# 3s_BMS.net
KiCad netlist of a schematic drawn in Altium Designer
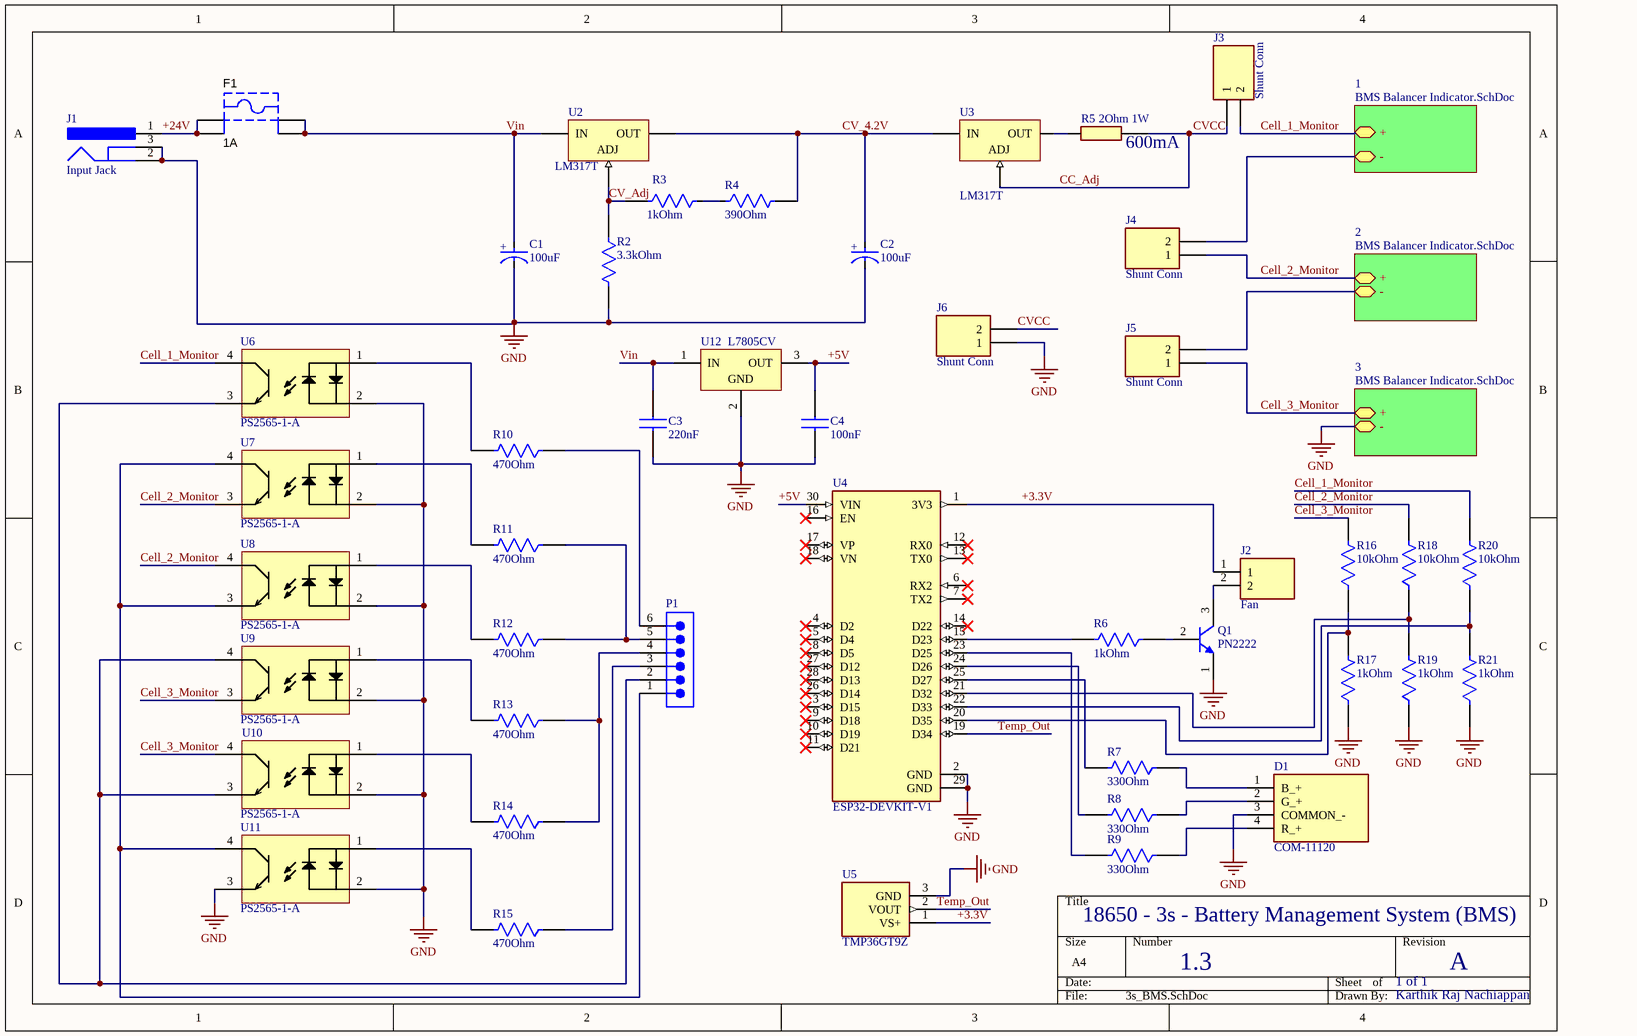
[diagram p0: 3s_BMS.SchDoc]

(export (version "E")
  (design (tool "Eeschema 10.0.6"))
  (components
    (comp (ref "C1")
      (value "100uF")
      (footprint "FP-RAD-TH-D_8_0_5-L_11_5-MFG")
      (description "Aluminum Electrolytic Capacitors (Radial Lead Type) 100uF ±20% 50V")
      (libsource (lib "Altium Content Vault") (part "a00bbbee19879c290e62620ae7e47b1"))
    )
    (comp (ref "C2")
      (value "100uF")
      (footprint "FP-RAD-TH-D_8_0_5-L_11_5-MFG")
      (description "Aluminum Electrolytic Capacitors (Radial Lead Type) 100uF ±20% 50V")
      (libsource (lib "Altium Content Vault") (part "a00bbbee19879c290e62620ae7e47b1"))
    )
    (comp (ref "C3")
      (value "220nF")
      (footprint "SamacSys:K224K20X7RF5TH5")
      (description "Capacitor")
      (fields
        (field (name "MANUFACTURER_PART_NUMBER") "K224K20X7RF5TH5")
        (field (name "MOUSER PART NUMBER") "594-K224K20X7RF5TH5")
      )
      (libsource (lib "*") (part "K224K20X7RF5TH5"))
    )
    (comp (ref "C4")
      (value "100nF")
      (footprint "SamacSys:C322C104K1R5TA")
      (description "Capacitor")
      (fields
        (field (name "MANUFACTURER_PART_NUMBER") "C322C104M5U5TA")
        (field (name "MOUSER PART NUMBER") "80-C322C104M5U")
      )
      (libsource (lib "*") (part "C322C104M5U5TA"))
    )
    (comp (ref "D1")
      (value "COM-11120")
      (footprint "SamacSys:COM11120")
      (description "LED")
      (fields (field (name "MOUSER PART NUMBER") "474-COM-11120"))
      (libsource (lib "*") (part "COM-11120"))
    )
    (comp (ref "F1")
      (value "1A")
      (footprint "KSTN-3557-2")
      (description "FUSE HOLDER, PCB MOUNT, 500VAC, 20A, ROHS")
      (fields (field (name "VOLTAGE") "500V") (field (name "MANUFACTURER") "Keystone-Electronics"))
      (libsource (lib "Altium Content Vault") (part "FUSE_HOLDER-4"))
    )
    (comp (ref "J1")
      (value "Input Jack")
      (footprint "CUI-PJ-002A_V")
      (fields (field (name "MANUFACTURER") "CUIInc."))
      (libsource (lib "Altium Content Vault") (part "JACK-2CD3-RN_B"))
    )
    (comp (ref "J2")
      (value "Fan")
      (footprint "SamacSys:HDRV2W67P0X254_1X2_467X234X823P")
      (description "Connector")
      (fields
        (field (name "MANUFACTURER_PART_NUMBER") "5-146277-2")
        (field (name "MOUSER PART NUMBER") "571-5-146277-2")
      )
      (libsource (lib "") (part "5-146277-2_2"))
    )
    (comp (ref "J3")
      (value "Shunt Conn")
      (footprint "SamacSys:HDRV2W67P0X254_1X2_467X234X823P")
      (description "Connector")
      (fields
        (field (name "MANUFACTURER_PART_NUMBER") "5-146277-2")
        (field (name "MOUSER PART NUMBER") "571-5-146277-2")
      )
      (libsource (lib "*") (part "5-146277-2"))
    )
    (comp (ref "J4")
      (value "Shunt Conn")
      (footprint "SamacSys:HDRV2W67P0X254_1X2_467X234X823P")
      (description "Connector")
      (fields
        (field (name "MANUFACTURER_PART_NUMBER") "5-146277-2")
        (field (name "MOUSER PART NUMBER") "571-5-146277-2")
      )
      (libsource (lib "") (part "5-146277-2_1"))
    )
    (comp (ref "J5")
      (value "Shunt Conn")
      (footprint "SamacSys:HDRV2W67P0X254_1X2_467X234X823P")
      (description "Connector")
      (fields
        (field (name "MANUFACTURER_PART_NUMBER") "5-146277-2")
        (field (name "MOUSER PART NUMBER") "571-5-146277-2")
      )
      (libsource (lib "") (part "5-146277-2_1"))
    )
    (comp (ref "J6")
      (value "Shunt Conn")
      (footprint "SamacSys:HDRV2W67P0X254_1X2_467X234X823P")
      (description "Connector")
      (fields
        (field (name "MANUFACTURER_PART_NUMBER") "5-146277-2")
        (field (name "MOUSER PART NUMBER") "571-5-146277-2")
      )
      (libsource (lib "") (part "5-146277-2_1"))
    )
    (comp (ref "P1")
      (value "~")
      (footprint "SMTC-TSW-106-07-X-S")
      (description "0.025\" SQ Post Header, Through-hole, Vertical, -55 to 125 degC, 2.54 mm Pitch, 6-Pin, Male, RoHS")
      (fields (field (name "MANUFACTURER") "Samtec") (field (name "PARTNUMBER") "TSW-106-07-G-S"))
      (libsource (lib "Altium Content Vault") (part "SMTC-TSW-106-X-X-S-X"))
    )
    (comp (ref "Q1")
      (value "PN2222")
      (footprint "FAIR-TO-92-3")
      (description "NPN General-Purpose Amplifier, 40 V, -55 to 150 degC, 3-Pin TO-92, RoHS, Tape and Reel")
      (fields (field (name "MANUFACTURER") "FairchildSemiconductor"))
      (libsource (lib "Altium Content Vault") (part "BJT-NPN-EBC-3"))
    )
    (comp (ref "R2")
      (value "3.3kOhm")
      (footprint "FP-MRS25-MFG")
      (description "RES 1K OHM 0.6W 1% AXIAL")
      (fields (field (name "TOLERANCE") "1%"))
      (libsource (lib "Altium Content Vault") (part "1029c3af85768c4190bb7ad29bc67b5"))
    )
    (comp (ref "R3")
      (value "1kOhm")
      (footprint "FP-MRS25-MFG")
      (description "RES 1K OHM 0.6W 1% AXIAL")
      (fields (field (name "TOLERANCE") "1%"))
      (libsource (lib "Altium Content Vault") (part "1029c3af85768c4190bb7ad29bc67b5"))
    )
    (comp (ref "R4")
      (value "390Ohm")
      (footprint "FP-MRS25-MFG")
      (description "RES 1K OHM 0.6W 1% AXIAL")
      (fields (field (name "TOLERANCE") "1%"))
      (libsource (lib "Altium Content Vault") (part "1029c3af85768c4190bb7ad29bc67b5"))
    )
    (comp (ref "R5")
      (value "2Ohm 1W")
      (footprint "SamacSys:RESAD1650W63L650D250")
      (description "Resistor")
      (fields
        (field (name "MANUFACTURER_PART_NUMBER") "PR01000102008JR500")
        (field (name "MOUSER PART NUMBER") "594-5073NW2R000J")
      )
      (libsource (lib "*") (part "PR01000102008JR500"))
    )
    (comp (ref "R6")
      (value "1kOhm")
      (footprint "FP-MRS25-MFG")
      (description "RES 1K OHM 0.6W 1% AXIAL")
      (fields (field (name "TOLERANCE") "1%"))
      (libsource (lib "Altium Content Vault") (part "1029c3af85768c4190bb7ad29bc67b5"))
    )
    (comp (ref "R7")
      (value "330Ohm")
      (footprint "FP-MRS25-MFG")
      (description "RES 1K OHM 0.6W 1% AXIAL")
      (fields (field (name "TOLERANCE") "1%"))
      (libsource (lib "Altium Content Vault") (part "1029c3af85768c4190bb7ad29bc67b5"))
    )
    (comp (ref "R8")
      (value "330Ohm")
      (footprint "FP-MRS25-MFG")
      (description "RES 1K OHM 0.6W 1% AXIAL")
      (fields (field (name "TOLERANCE") "1%"))
      (libsource (lib "Altium Content Vault") (part "1029c3af85768c4190bb7ad29bc67b5"))
    )
    (comp (ref "R9")
      (value "330Ohm")
      (footprint "FP-MRS25-MFG")
      (description "RES 1K OHM 0.6W 1% AXIAL")
      (fields (field (name "TOLERANCE") "1%"))
      (libsource (lib "Altium Content Vault") (part "1029c3af85768c4190bb7ad29bc67b5"))
    )
    (comp (ref "R10")
      (value "470Ohm")
      (footprint "FP-MRS25-MFG")
      (description "RES 1K OHM 0.6W 1% AXIAL")
      (fields (field (name "TOLERANCE") "1%"))
      (libsource (lib "Altium Content Vault") (part "1029c3af85768c4190bb7ad29bc67b5"))
    )
    (comp (ref "R11")
      (value "470Ohm")
      (footprint "FP-MRS25-MFG")
      (description "RES 1K OHM 0.6W 1% AXIAL")
      (fields (field (name "TOLERANCE") "1%"))
      (libsource (lib "Altium Content Vault") (part "1029c3af85768c4190bb7ad29bc67b5"))
    )
    (comp (ref "R12")
      (value "470Ohm")
      (footprint "FP-MRS25-MFG")
      (description "RES 1K OHM 0.6W 1% AXIAL")
      (fields (field (name "TOLERANCE") "1%"))
      (libsource (lib "Altium Content Vault") (part "1029c3af85768c4190bb7ad29bc67b5"))
    )
    (comp (ref "R13")
      (value "470Ohm")
      (footprint "FP-MRS25-MFG")
      (description "RES 1K OHM 0.6W 1% AXIAL")
      (fields (field (name "TOLERANCE") "1%"))
      (libsource (lib "Altium Content Vault") (part "1029c3af85768c4190bb7ad29bc67b5"))
    )
    (comp (ref "R14")
      (value "470Ohm")
      (footprint "FP-MRS25-MFG")
      (description "RES 1K OHM 0.6W 1% AXIAL")
      (fields (field (name "TOLERANCE") "1%"))
      (libsource (lib "Altium Content Vault") (part "1029c3af85768c4190bb7ad29bc67b5"))
    )
    (comp (ref "R15")
      (value "470Ohm")
      (footprint "FP-MRS25-MFG")
      (description "RES 1K OHM 0.6W 1% AXIAL")
      (fields (field (name "TOLERANCE") "1%"))
      (libsource (lib "Altium Content Vault") (part "1029c3af85768c4190bb7ad29bc67b5"))
    )
    (comp (ref "R16")
      (value "10kOhm")
      (footprint "FP-MRS25-MFG")
      (description "RES 1K OHM 0.6W 1% AXIAL")
      (fields (field (name "TOLERANCE") "1%"))
      (libsource (lib "Altium Content Vault") (part "1029c3af85768c4190bb7ad29bc67b5"))
    )
    (comp (ref "R17")
      (value "1kOhm")
      (footprint "FP-MRS25-MFG")
      (description "RES 1K OHM 0.6W 1% AXIAL")
      (fields (field (name "TOLERANCE") "1%"))
      (libsource (lib "Altium Content Vault") (part "1029c3af85768c4190bb7ad29bc67b5"))
    )
    (comp (ref "R18")
      (value "10kOhm")
      (footprint "FP-MRS25-MFG")
      (description "RES 1K OHM 0.6W 1% AXIAL")
      (fields (field (name "TOLERANCE") "1%"))
      (libsource (lib "Altium Content Vault") (part "1029c3af85768c4190bb7ad29bc67b5"))
    )
    (comp (ref "R19")
      (value "1kOhm")
      (footprint "FP-MRS25-MFG")
      (description "RES 1K OHM 0.6W 1% AXIAL")
      (fields (field (name "TOLERANCE") "1%"))
      (libsource (lib "Altium Content Vault") (part "1029c3af85768c4190bb7ad29bc67b5"))
    )
    (comp (ref "R20")
      (value "10kOhm")
      (footprint "FP-MRS25-MFG")
      (description "RES 1K OHM 0.6W 1% AXIAL")
      (fields (field (name "TOLERANCE") "1%"))
      (libsource (lib "Altium Content Vault") (part "1029c3af85768c4190bb7ad29bc67b5"))
    )
    (comp (ref "R21")
      (value "1kOhm")
      (footprint "FP-MRS25-MFG")
      (description "RES 1K OHM 0.6W 1% AXIAL")
      (fields (field (name "TOLERANCE") "1%"))
      (libsource (lib "Altium Content Vault") (part "1029c3af85768c4190bb7ad29bc67b5"))
    )
    (comp (ref "U2")
      (value "LM317T")
      (footprint "TO-220")
      (description "1.5A, 1.2V to 37V Adjustable Voltage Regulator, 3-Pin TO-220")
      (libsource (lib "Altium Content Vault") (part "PM-REG-117-SIL3"))
    )
    (comp (ref "U3")
      (value "LM317T")
      (footprint "TO-220")
      (description "1.5A, 1.2V to 37V Adjustable Voltage Regulator, 3-Pin TO-220")
      (libsource (lib "Altium Content Vault") (part "PM-REG-117-SIL3"))
    )
    (comp (ref "U4")
      (value "ESP32-DEVKIT-V1")
      (footprint "MODULE_ESP32_DEVKIT_V1")
      (fields (field (name "MF") "Do it"))
      (libsource (lib "NTU") (part "ESP32-DEVKIT-V1"))
    )
    (comp (ref "U5")
      (value "TMP36GT9Z")
      (footprint "SamacSys:TO-92")
      (description "Thermistor")
      (fields (field (name "MOUSER PART NUMBER") "584-TMP36GT9Z"))
      (libsource (lib "*") (part "TMP36GT9Z"))
    )
    (comp (ref "U6")
      (value "PS2565-1-A")
      (footprint "DIP762W50P254L460H455Q4B")
      (description "PS2565-1-A Optocoupler AC-IN 1-CH Transistor DC-OUT 4-Pin PDIP Magazine")
      (libsource (lib "Altium Content Vault") (part "PS2565-1-A"))
    )
    (comp (ref "U7")
      (value "PS2565-1-A")
      (footprint "DIP762W50P254L460H455Q4B")
      (description "PS2565-1-A Optocoupler AC-IN 1-CH Transistor DC-OUT 4-Pin PDIP Magazine")
      (libsource (lib "Altium Content Vault") (part "PS2565-1-A"))
    )
    (comp (ref "U8")
      (value "PS2565-1-A")
      (footprint "DIP762W50P254L460H455Q4B")
      (description "PS2565-1-A Optocoupler AC-IN 1-CH Transistor DC-OUT 4-Pin PDIP Magazine")
      (libsource (lib "Altium Content Vault") (part "PS2565-1-A"))
    )
    (comp (ref "U9")
      (value "PS2565-1-A")
      (footprint "DIP762W50P254L460H455Q4B")
      (description "PS2565-1-A Optocoupler AC-IN 1-CH Transistor DC-OUT 4-Pin PDIP Magazine")
      (libsource (lib "Altium Content Vault") (part "PS2565-1-A"))
    )
    (comp (ref "U10")
      (value "PS2565-1-A")
      (footprint "DIP762W50P254L460H455Q4B")
      (description "PS2565-1-A Optocoupler AC-IN 1-CH Transistor DC-OUT 4-Pin PDIP Magazine")
      (libsource (lib "Altium Content Vault") (part "PS2565-1-A"))
    )
    (comp (ref "U11")
      (value "PS2565-1-A")
      (footprint "DIP762W50P254L460H455Q4B")
      (description "PS2565-1-A Optocoupler AC-IN 1-CH Transistor DC-OUT 4-Pin PDIP Magazine")
      (libsource (lib "Altium Content Vault") (part "PS2565-1-A"))
    )
    (comp (ref "U12")
      (value "L7805CV")
      (footprint "TO220")
      (description "Positive Voltage Regulator, 5V, 3-Pin TO-220")
      (libsource (lib "Altium Content Vault") (part "PM-REG-L4940-SIL3"))
    )
  )
  (nets
    (net (code "1") (name "/+3.3V") (class "Default")
      (node (ref "J2") (pin "1") (pinfunction "1_1") (pintype "passive"))
      (node (ref "U4") (pin "1") (pinfunction "3V3_1") (pintype "output"))
      (node (ref "U5") (pin "1") (pinfunction "VS+_1") (pintype "power_in"))
    )
    (net (code "2") (name "/+5V") (class "Default")
      (node (ref "C4") (pin "1") (pinfunction "+_1") (pintype "passive"))
      (node (ref "U12") (pin "3") (pinfunction "OUT_3") (pintype "power_in"))
      (node (ref "U4") (pin "30") (pinfunction "VIN_30") (pintype "input"))
    )
    (net (code "3") (name "/+24V") (class "Default")
      (node (ref "F1") (pin "1") (pinfunction "1_1") (pintype "passive"))
      (node (ref "F1") (pin "2") (pinfunction "2_2") (pintype "passive"))
      (node (ref "J1") (pin "1") (pinfunction "1_1") (pintype "passive"))
    )
    (net (code "4") (name "/-") (class "Default")
      (node (ref "J5") (pin "2") (pinfunction "2_2") (pintype "passive"))
    )
    (net (code "5") (name "/-_1") (class "Default")
      (node (ref "J4") (pin "2") (pinfunction "2_2") (pintype "passive"))
    )
    (net (code "6") (name "/CC_Adj") (class "Default")
      (node (ref "J3") (pin "1") (pinfunction "1_1") (pintype "passive"))
      (node (ref "J6") (pin "2") (pinfunction "2_2") (pintype "passive"))
      (node (ref "R5") (pin "2") (pinfunction "2_2") (pintype "passive"))
      (node (ref "U3") (pin "1") (pinfunction "ADJ_1") (pintype "input"))
    )
    (net (code "7") (name "/CV_4.2V") (class "Default")
      (node (ref "C2") (pin "2") (pinfunction "A_2") (pintype "passive"))
      (node (ref "R4") (pin "2") (pinfunction "2_2") (pintype "passive"))
      (node (ref "U2") (pin "2") (pinfunction "OUT_2") (pintype "power_in"))
      (node (ref "U3") (pin "3") (pinfunction "IN_3") (pintype "power_in"))
    )
    (net (code "8") (name "/CV_Adj") (class "Default")
      (node (ref "R2") (pin "1") (pinfunction "1_1") (pintype "passive"))
      (node (ref "R3") (pin "1") (pinfunction "1_1") (pintype "passive"))
      (node (ref "U2") (pin "1") (pinfunction "ADJ_1") (pintype "input"))
    )
    (net (code "9") (name "/Cell_1_Monitor") (class "Default")
      (node (ref "J3") (pin "2") (pinfunction "2_2") (pintype "passive"))
      (node (ref "R20") (pin "2") (pinfunction "2_2") (pintype "passive"))
      (node (ref "U6") (pin "4") (pinfunction "Collector_4") (pintype "power_in"))
    )
    (net (code "10") (name "/Cell_2_Monitor") (class "Default")
      (node (ref "J4") (pin "1") (pinfunction "1_1") (pintype "passive"))
      (node (ref "R18") (pin "2") (pinfunction "2_2") (pintype "passive"))
      (node (ref "U7") (pin "3") (pinfunction "Emitter_3") (pintype "power_in"))
      (node (ref "U8") (pin "4") (pinfunction "Collector_4") (pintype "power_in"))
    )
    (net (code "11") (name "/Cell_3_Monitor") (class "Default")
      (node (ref "J5") (pin "1") (pinfunction "1_1") (pintype "passive"))
      (node (ref "R16") (pin "2") (pinfunction "2_2") (pintype "passive"))
      (node (ref "U10") (pin "4") (pinfunction "Collector_4") (pintype "power_in"))
      (node (ref "U9") (pin "3") (pinfunction "Emitter_3") (pintype "power_in"))
    )
    (net (code "12") (name "/Temp_Out") (class "Default")
      (node (ref "U4") (pin "19") (pinfunction "D34_19") (pintype "bidirectional"))
      (node (ref "U5") (pin "2") (pinfunction "VOUT_2") (pintype "output"))
    )
    (net (code "13") (name "/Vin") (class "Default")
      (node (ref "C1") (pin "2") (pinfunction "A_2") (pintype "passive"))
      (node (ref "C3") (pin "1") (pinfunction "1_1") (pintype "passive"))
      (node (ref "F1") (pin "3") (pinfunction "3_3") (pintype "passive"))
      (node (ref "F1") (pin "4") (pinfunction "4_4") (pintype "passive"))
      (node (ref "U12") (pin "1") (pinfunction "IN_1") (pintype "power_in"))
      (node (ref "U2") (pin "3") (pinfunction "IN_3") (pintype "power_in"))
    )
    (net (code "14") (name "GND") (class "Default")
      (node (ref "C1") (pin "1") (pinfunction "C_1") (pintype "passive"))
      (node (ref "C2") (pin "1") (pinfunction "C_1") (pintype "passive"))
      (node (ref "C3") (pin "2") (pinfunction "2_2") (pintype "passive"))
      (node (ref "C4") (pin "2") (pinfunction "-_2") (pintype "passive"))
      (node (ref "D1") (pin "3") (pinfunction "COMMON_-_3") (pintype "passive"))
      (node (ref "J1") (pin "2") (pinfunction "2_2") (pintype "passive"))
      (node (ref "J1") (pin "3") (pinfunction "3_3") (pintype "passive"))
      (node (ref "J6") (pin "1") (pinfunction "1_1") (pintype "passive"))
      (node (ref "Q1") (pin "1") (pinfunction "E_1") (pintype "passive"))
      (node (ref "R17") (pin "1") (pinfunction "1_1") (pintype "passive"))
      (node (ref "R19") (pin "1") (pinfunction "1_1") (pintype "passive"))
      (node (ref "R2") (pin "2") (pinfunction "2_2") (pintype "passive"))
      (node (ref "R21") (pin "1") (pinfunction "1_1") (pintype "passive"))
      (node (ref "U10") (pin "2") (pinfunction "Cathode_2") (pintype "passive"))
      (node (ref "U11") (pin "2") (pinfunction "Cathode_2") (pintype "passive"))
      (node (ref "U11") (pin "3") (pinfunction "Emitter_3") (pintype "power_in"))
      (node (ref "U12") (pin "2") (pinfunction "GND_2") (pintype "power_in"))
      (node (ref "U4") (pin "2") (pinfunction "GND_2") (pintype "power_in"))
      (node (ref "U4") (pin "29") (pinfunction "GND_29") (pintype "power_in"))
      (node (ref "U5") (pin "3") (pinfunction "GND_3") (pintype "power_in"))
      (node (ref "U6") (pin "2") (pinfunction "Cathode_2") (pintype "passive"))
      (node (ref "U7") (pin "2") (pinfunction "Cathode_2") (pintype "passive"))
      (node (ref "U8") (pin "2") (pinfunction "Cathode_2") (pintype "passive"))
      (node (ref "U9") (pin "2") (pinfunction "Cathode_2") (pintype "passive"))
    )
    (net (code "15") (name "Net-(D1-B_+)") (class "Default")
      (node (ref "D1") (pin "1") (pinfunction "B_+_1") (pintype "passive"))
      (node (ref "R7") (pin "1") (pinfunction "1_1") (pintype "passive"))
    )
    (net (code "16") (name "Net-(D1-G_+)") (class "Default")
      (node (ref "D1") (pin "2") (pinfunction "G_+_2") (pintype "passive"))
      (node (ref "R8") (pin "1") (pinfunction "1_1") (pintype "passive"))
    )
    (net (code "17") (name "Net-(D1-R_+)") (class "Default")
      (node (ref "D1") (pin "4") (pinfunction "R_+_4") (pintype "passive"))
      (node (ref "R9") (pin "1") (pinfunction "1_1") (pintype "passive"))
    )
    (net (code "18") (name "Net-(P1-Pad3)") (class "Default")
      (node (ref "P1") (pin "3") (pinfunction "3_3") (pintype "passive"))
      (node (ref "R15") (pin "1") (pinfunction "1_1") (pintype "passive"))
    )
    (net (code "19") (name "Net-(P1-Pad4)") (class "Default")
      (node (ref "P1") (pin "4") (pinfunction "4_4") (pintype "passive"))
      (node (ref "R13") (pin "1") (pinfunction "1_1") (pintype "passive"))
      (node (ref "R14") (pin "1") (pinfunction "1_1") (pintype "passive"))
    )
    (net (code "20") (name "Net-(P1-Pad5)") (class "Default")
      (node (ref "P1") (pin "5") (pinfunction "5_5") (pintype "passive"))
      (node (ref "R11") (pin "1") (pinfunction "1_1") (pintype "passive"))
      (node (ref "R12") (pin "1") (pinfunction "1_1") (pintype "passive"))
    )
    (net (code "21") (name "Net-(P1-Pad6)") (class "Default")
      (node (ref "P1") (pin "6") (pinfunction "6_6") (pintype "passive"))
      (node (ref "R10") (pin "1") (pinfunction "1_1") (pintype "passive"))
    )
    (net (code "22") (name "Net-(Q1-B)") (class "Default")
      (node (ref "Q1") (pin "2") (pinfunction "B_2") (pintype "passive"))
      (node (ref "R6") (pin "1") (pinfunction "1_1") (pintype "passive"))
    )
    (net (code "23") (name "Net-(Q1-C)") (class "Default")
      (node (ref "J2") (pin "2") (pinfunction "2_2") (pintype "passive"))
      (node (ref "Q1") (pin "3") (pinfunction "C_3") (pintype "passive"))
    )
    (net (code "24") (name "Net-(R3-Pad2)") (class "Default")
      (node (ref "R3") (pin "2") (pinfunction "2_2") (pintype "passive"))
      (node (ref "R4") (pin "1") (pinfunction "1_1") (pintype "passive"))
    )
    (net (code "25") (name "Net-(U3-OUT)") (class "Default")
      (node (ref "R5") (pin "1") (pinfunction "1_1") (pintype "passive"))
      (node (ref "U3") (pin "2") (pinfunction "OUT_2") (pintype "power_in"))
    )
    (net (code "26") (name "Net-(U4-D23)") (class "Default")
      (node (ref "R6") (pin "2") (pinfunction "2_2") (pintype "passive"))
      (node (ref "U4") (pin "15") (pinfunction "D23_15") (pintype "bidirectional"))
    )
    (net (code "27") (name "Net-(U4-D25)") (class "Default")
      (node (ref "R9") (pin "2") (pinfunction "2_2") (pintype "passive"))
      (node (ref "U4") (pin "23") (pinfunction "D25_23") (pintype "bidirectional"))
    )
    (net (code "28") (name "Net-(U4-D26)") (class "Default")
      (node (ref "R8") (pin "2") (pinfunction "2_2") (pintype "passive"))
      (node (ref "U4") (pin "24") (pinfunction "D26_24") (pintype "bidirectional"))
    )
    (net (code "29") (name "Net-(U4-D27)") (class "Default")
      (node (ref "R7") (pin "2") (pinfunction "2_2") (pintype "passive"))
      (node (ref "U4") (pin "25") (pinfunction "D27_25") (pintype "bidirectional"))
    )
    (net (code "30") (name "Net-(U4-D32)") (class "Default")
      (node (ref "R18") (pin "1") (pinfunction "1_1") (pintype "passive"))
      (node (ref "R19") (pin "2") (pinfunction "2_2") (pintype "passive"))
      (node (ref "U4") (pin "21") (pinfunction "D32_21") (pintype "bidirectional"))
    )
    (net (code "31") (name "Net-(U4-D33)") (class "Default")
      (node (ref "R20") (pin "1") (pinfunction "1_1") (pintype "passive"))
      (node (ref "R21") (pin "2") (pinfunction "2_2") (pintype "passive"))
      (node (ref "U4") (pin "22") (pinfunction "D33_22") (pintype "bidirectional"))
    )
    (net (code "32") (name "Net-(U4-D35)") (class "Default")
      (node (ref "R16") (pin "1") (pinfunction "1_1") (pintype "passive"))
      (node (ref "R17") (pin "2") (pinfunction "2_2") (pintype "passive"))
      (node (ref "U4") (pin "20") (pinfunction "D35_20") (pintype "bidirectional"))
    )
    (net (code "33") (name "Net-(U6-Anode)") (class "Default")
      (node (ref "R10") (pin "2") (pinfunction "2_2") (pintype "passive"))
      (node (ref "U6") (pin "1") (pinfunction "Anode_1") (pintype "passive"))
    )
    (net (code "34") (name "Net-(U7-Anode)") (class "Default")
      (node (ref "R11") (pin "2") (pinfunction "2_2") (pintype "passive"))
      (node (ref "U7") (pin "1") (pinfunction "Anode_1") (pintype "passive"))
    )
    (net (code "35") (name "Net-(U8-Anode)") (class "Default")
      (node (ref "R12") (pin "2") (pinfunction "2_2") (pintype "passive"))
      (node (ref "U8") (pin "1") (pinfunction "Anode_1") (pintype "passive"))
    )
    (net (code "36") (name "Net-(U9-Anode)") (class "Default")
      (node (ref "R13") (pin "2") (pinfunction "2_2") (pintype "passive"))
      (node (ref "U9") (pin "1") (pinfunction "Anode_1") (pintype "passive"))
    )
    (net (code "37") (name "Net-(U10-Anode)") (class "Default")
      (node (ref "R14") (pin "2") (pinfunction "2_2") (pintype "passive"))
      (node (ref "U10") (pin "1") (pinfunction "Anode_1") (pintype "passive"))
    )
    (net (code "38") (name "Net-(U10-Emitter)") (class "Default")
      (node (ref "P1") (pin "2") (pinfunction "2_2") (pintype "passive"))
      (node (ref "U10") (pin "3") (pinfunction "Emitter_3") (pintype "power_in"))
      (node (ref "U6") (pin "3") (pinfunction "Emitter_3") (pintype "power_in"))
      (node (ref "U9") (pin "4") (pinfunction "Collector_4") (pintype "power_in"))
    )
    (net (code "39") (name "Net-(U11-Anode)") (class "Default")
      (node (ref "R15") (pin "2") (pinfunction "2_2") (pintype "passive"))
      (node (ref "U11") (pin "1") (pinfunction "Anode_1") (pintype "passive"))
    )
    (net (code "40") (name "Net-(U11-Collector)") (class "Default")
      (node (ref "P1") (pin "1") (pinfunction "1_1") (pintype "passive"))
      (node (ref "U11") (pin "4") (pinfunction "Collector_4") (pintype "power_in"))
      (node (ref "U7") (pin "4") (pinfunction "Collector_4") (pintype "power_in"))
      (node (ref "U8") (pin "3") (pinfunction "Emitter_3") (pintype "power_in"))
    )
    (net (code "41") (name "unconnected-(U4-D2-Pad4)") (class "Default")
      (node (ref "U4") (pin "4") (pinfunction "D2_4") (pintype "bidirectional+no_connect"))
    )
    (net (code "42") (name "unconnected-(U4-D4-Pad5)") (class "Default")
      (node (ref "U4") (pin "5") (pinfunction "D4_5") (pintype "bidirectional+no_connect"))
    )
    (net (code "43") (name "unconnected-(U4-D5-Pad8)") (class "Default")
      (node (ref "U4") (pin "8") (pinfunction "D5_8") (pintype "bidirectional+no_connect"))
    )
    (net (code "44") (name "unconnected-(U4-D12-Pad27)") (class "Default")
      (node (ref "U4") (pin "27") (pinfunction "D12_27") (pintype "bidirectional+no_connect"))
    )
    (net (code "45") (name "unconnected-(U4-D13-Pad28)") (class "Default")
      (node (ref "U4") (pin "28") (pinfunction "D13_28") (pintype "bidirectional+no_connect"))
    )
    (net (code "46") (name "unconnected-(U4-D14-Pad26)") (class "Default")
      (node (ref "U4") (pin "26") (pinfunction "D14_26") (pintype "bidirectional+no_connect"))
    )
    (net (code "47") (name "unconnected-(U4-D15-Pad3)") (class "Default")
      (node (ref "U4") (pin "3") (pinfunction "D15_3") (pintype "bidirectional+no_connect"))
    )
    (net (code "48") (name "unconnected-(U4-D18-Pad9)") (class "Default")
      (node (ref "U4") (pin "9") (pinfunction "D18_9") (pintype "bidirectional+no_connect"))
    )
    (net (code "49") (name "unconnected-(U4-D19-Pad10)") (class "Default")
      (node (ref "U4") (pin "10") (pinfunction "D19_10") (pintype "bidirectional+no_connect"))
    )
    (net (code "50") (name "unconnected-(U4-D21-Pad11)") (class "Default")
      (node (ref "U4") (pin "11") (pinfunction "D21_11") (pintype "bidirectional+no_connect"))
    )
    (net (code "51") (name "unconnected-(U4-D22-Pad14)") (class "Default")
      (node (ref "U4") (pin "14") (pinfunction "D22_14") (pintype "bidirectional+no_connect"))
    )
    (net (code "52") (name "unconnected-(U4-EN-Pad16)") (class "Default")
      (node (ref "U4") (pin "16") (pinfunction "EN_16") (pintype "input+no_connect"))
    )
    (net (code "53") (name "unconnected-(U4-RX0-Pad12)") (class "Default")
      (node (ref "U4") (pin "12") (pinfunction "RX0_12") (pintype "input+no_connect"))
    )
    (net (code "54") (name "unconnected-(U4-RX2-Pad6)") (class "Default")
      (node (ref "U4") (pin "6") (pinfunction "RX2_6") (pintype "input+no_connect"))
    )
    (net (code "55") (name "unconnected-(U4-TX0-Pad13)") (class "Default")
      (node (ref "U4") (pin "13") (pinfunction "TX0_13") (pintype "output+no_connect"))
    )
    (net (code "56") (name "unconnected-(U4-TX2-Pad7)") (class "Default")
      (node (ref "U4") (pin "7") (pinfunction "TX2_7") (pintype "output+no_connect"))
    )
    (net (code "57") (name "unconnected-(U4-VN-Pad18)") (class "Default")
      (node (ref "U4") (pin "18") (pinfunction "VN_18") (pintype "bidirectional+no_connect"))
    )
    (net (code "58") (name "unconnected-(U4-VP-Pad17)") (class "Default")
      (node (ref "U4") (pin "17") (pinfunction "VP_17") (pintype "bidirectional+no_connect"))
    )
  )
)
